# WiFi_DAC2.net
KiCad netlist of a schematic drawn in EAGLE
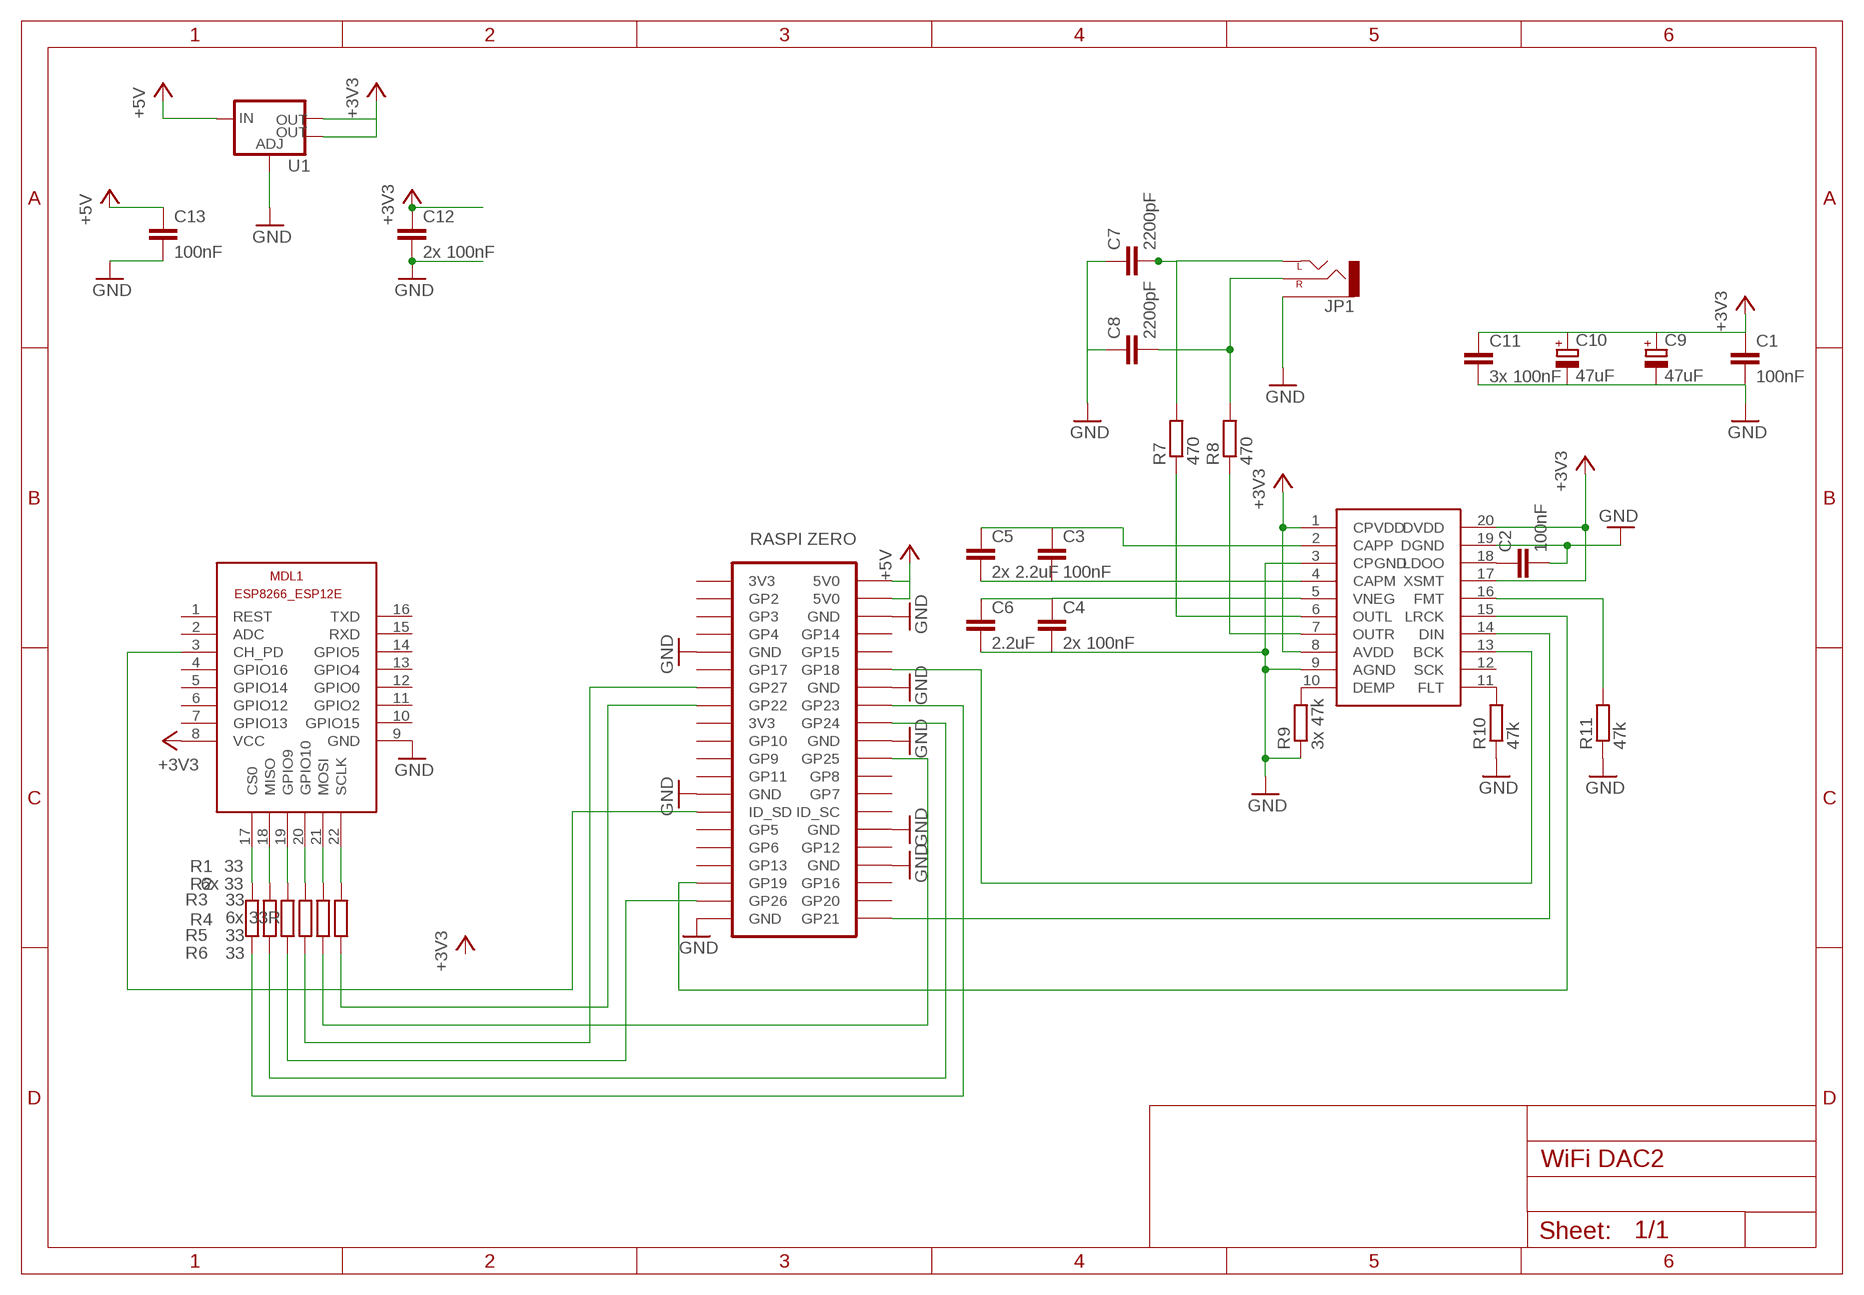
[diagram p0: schematic, sheet 1]

(export (version "E")
  (design (tool "Eeschema 10.0.6"))
  (components
    (comp (ref "C1")
      (value "100nF")
      (footprint "eagle-import:C0603")
      (libsource (lib "eagle-import") (part "C-EUC0603"))
    )
    (comp (ref "C2")
      (value "100nF")
      (footprint "eagle-import:C0603")
      (libsource (lib "eagle-import") (part "C-EUC0603"))
    )
    (comp (ref "C3")
      (value "100nF")
      (footprint "eagle-import:C0603")
      (libsource (lib "eagle-import") (part "C-EUC0603"))
    )
    (comp (ref "C4")
      (value "2x 100nF")
      (footprint "eagle-import:C0603")
      (libsource (lib "eagle-import") (part "C-EUC0603"))
    )
    (comp (ref "C5")
      (value "2x 2.2uF")
      (footprint "eagle-import:C0603")
      (libsource (lib "eagle-import") (part "C-EUC0603"))
    )
    (comp (ref "C6")
      (value "2.2uF")
      (footprint "eagle-import:C0603")
      (libsource (lib "eagle-import") (part "C-EUC0603"))
    )
    (comp (ref "C7")
      (value "2200pF")
      (footprint "eagle-import:C0603")
      (libsource (lib "eagle-import") (part "C-EUC0603"))
    )
    (comp (ref "C8")
      (value "2200pF")
      (footprint "eagle-import:C0603")
      (libsource (lib "eagle-import") (part "C-EUC0603"))
    )
    (comp (ref "C9")
      (value "47uF")
      (footprint "eagle-import:SANYO-OSCON_SMD_A5")
      (libsource (lib "eagle-import") (part "CPOL-EUSANYO_SMD_A5"))
    )
    (comp (ref "C10")
      (value "47uF")
      (footprint "eagle-import:SANYO-OSCON_SMD_A5")
      (libsource (lib "eagle-import") (part "CPOL-EUSANYO_SMD_A5"))
    )
    (comp (ref "C11")
      (value "3x 100nF")
      (footprint "eagle-import:C0603")
      (libsource (lib "eagle-import") (part "C-EUC0603"))
    )
    (comp (ref "C12")
      (value "2x 100nF")
      (footprint "eagle-import:C0603")
      (libsource (lib "eagle-import") (part "C-EUC0603"))
    )
    (comp (ref "C13")
      (value "100nF")
      (footprint "eagle-import:C0603")
      (libsource (lib "eagle-import") (part "C-EUC0603"))
    )
    (comp (ref "JP1")
      (value "AUDIO-JACKPTH")
      (footprint "eagle-import:AUDIO-JACK")
      (libsource (lib "eagle-import") (part "AUDIO-JACKPTH"))
    )
    (comp (ref "MDL1")
      (value "ESP8266-12EESP8266-ESP12E")
      (footprint "eagle-import:ESP8266-ESP12E")
      (libsource (lib "eagle-import") (part "ESP8266-12EESP8266-ESP12E"))
    )
    (comp (ref "R1")
      (value "33")
      (footprint "eagle-import:R0603")
      (libsource (lib "eagle-import") (part "R-EU_R0603"))
    )
    (comp (ref "R2")
      (value "6x 33")
      (footprint "eagle-import:R0603")
      (libsource (lib "eagle-import") (part "R-EU_R0603"))
    )
    (comp (ref "R3")
      (value "33")
      (footprint "eagle-import:R0603")
      (libsource (lib "eagle-import") (part "R-EU_R0603"))
    )
    (comp (ref "R4")
      (value "6x 33R")
      (footprint "eagle-import:R0603")
      (libsource (lib "eagle-import") (part "R-EU_R0603"))
    )
    (comp (ref "R5")
      (value "33")
      (footprint "eagle-import:R0603")
      (libsource (lib "eagle-import") (part "R-EU_R0603"))
    )
    (comp (ref "R6")
      (value "33")
      (footprint "eagle-import:R0603")
      (libsource (lib "eagle-import") (part "R-EU_R0603"))
    )
    (comp (ref "R7")
      (value "470")
      (footprint "eagle-import:R0603")
      (libsource (lib "eagle-import") (part "R-EU_R0603"))
    )
    (comp (ref "R8")
      (value "470")
      (footprint "eagle-import:R0603")
      (libsource (lib "eagle-import") (part "R-EU_R0603"))
    )
    (comp (ref "R9")
      (value "3x 47k")
      (footprint "eagle-import:R0603")
      (libsource (lib "eagle-import") (part "R-EU_R0603"))
    )
    (comp (ref "R10")
      (value "47k")
      (footprint "eagle-import:R0603")
      (libsource (lib "eagle-import") (part "R-EU_R0603"))
    )
    (comp (ref "R11")
      (value "47k")
      (footprint "eagle-import:R0603")
      (libsource (lib "eagle-import") (part "R-EU_R0603"))
    )
    (comp (ref "U$1")
      (value "ZERO")
      (footprint "eagle-import:ZERO")
      (libsource (lib "eagle-import") (part "ZERO"))
    )
    (comp (ref "U$2")
      (value "PCM5102")
      (footprint "eagle-import:TSSOP20")
      (libsource (lib "eagle-import") (part "PCM5102"))
    )
    (comp (ref "U1")
      (value "V_REG_LM1117SOT223")
      (footprint "eagle-import:SOT223")
      (libsource (lib "eagle-import") (part "V_REG_LM1117SOT223"))
    )
  )
  (nets
    (net (code "1") (name "+3V3") (class "Default")
      (node (ref "C1") (pin "1") (pinfunction "1_1") (pintype "passive"))
      (node (ref "C10") (pin "+") (pinfunction "+_+") (pintype "passive"))
      (node (ref "C11") (pin "1") (pinfunction "1_1") (pintype "passive"))
      (node (ref "C12") (pin "1") (pinfunction "1_1") (pintype "passive"))
      (node (ref "C9") (pin "+") (pinfunction "+_+") (pintype "passive"))
      (node (ref "MDL1") (pin "8") (pinfunction "VCC_8") (pintype "bidirectional"))
      (node (ref "U$2") (pin "1") (pinfunction "CPVDD_1") (pintype "bidirectional"))
      (node (ref "U$2") (pin "17") (pinfunction "XSMT_17") (pintype "bidirectional"))
      (node (ref "U$2") (pin "20") (pinfunction "DVDD_20") (pintype "bidirectional"))
      (node (ref "U$2") (pin "8") (pinfunction "AVDD_8") (pintype "bidirectional"))
      (node (ref "U1") (pin "2") (pinfunction "OUT_2") (pintype "output"))
      (node (ref "U1") (pin "4") (pinfunction "OUT_4") (pintype "output"))
    )
    (net (code "2") (name "+5V") (class "Default")
      (node (ref "C13") (pin "1") (pinfunction "1_1") (pintype "passive"))
      (node (ref "U$1") (pin "2") (pinfunction "5V0_2") (pintype "bidirectional"))
      (node (ref "U$1") (pin "4") (pinfunction "5V0_4") (pintype "bidirectional"))
      (node (ref "U1") (pin "3") (pinfunction "IN_3") (pintype "input"))
    )
    (net (code "3") (name "GND") (class "Default")
      (node (ref "C1") (pin "2") (pinfunction "2_2") (pintype "passive"))
      (node (ref "C10") (pin "-") (pinfunction "-_-") (pintype "passive"))
      (node (ref "C11") (pin "2") (pinfunction "2_2") (pintype "passive"))
      (node (ref "C12") (pin "2") (pinfunction "2_2") (pintype "passive"))
      (node (ref "C13") (pin "2") (pinfunction "2_2") (pintype "passive"))
      (node (ref "C2") (pin "2") (pinfunction "2_2") (pintype "passive"))
      (node (ref "C4") (pin "2") (pinfunction "2_2") (pintype "passive"))
      (node (ref "C6") (pin "2") (pinfunction "2_2") (pintype "passive"))
      (node (ref "C7") (pin "1") (pinfunction "1_1") (pintype "passive"))
      (node (ref "C8") (pin "1") (pinfunction "1_1") (pintype "passive"))
      (node (ref "C9") (pin "-") (pinfunction "-_-") (pintype "passive"))
      (node (ref "JP1") (pin "SLEEVE") (pinfunction "SLEEVE_SLEEVE") (pintype "bidirectional"))
      (node (ref "MDL1") (pin "9") (pinfunction "GND_9") (pintype "bidirectional"))
      (node (ref "R10") (pin "1") (pinfunction "1_1") (pintype "passive"))
      (node (ref "R11") (pin "1") (pinfunction "1_1") (pintype "passive"))
      (node (ref "R9") (pin "1") (pinfunction "1_1") (pintype "passive"))
      (node (ref "U$1") (pin "14") (pinfunction "GND_14") (pintype "bidirectional"))
      (node (ref "U$1") (pin "20") (pinfunction "GND_20") (pintype "bidirectional"))
      (node (ref "U$1") (pin "25") (pinfunction "GND_25") (pintype "bidirectional"))
      (node (ref "U$1") (pin "30") (pinfunction "GND_30") (pintype "bidirectional"))
      (node (ref "U$1") (pin "34") (pinfunction "GND_34") (pintype "bidirectional"))
      (node (ref "U$1") (pin "39") (pinfunction "GND_39") (pintype "bidirectional"))
      (node (ref "U$1") (pin "6") (pinfunction "GND_6") (pintype "bidirectional"))
      (node (ref "U$1") (pin "9") (pinfunction "GND_9") (pintype "bidirectional"))
      (node (ref "U$2") (pin "19") (pinfunction "DGND_19") (pintype "bidirectional"))
      (node (ref "U$2") (pin "3") (pinfunction "CPGND_3") (pintype "bidirectional"))
      (node (ref "U$2") (pin "9") (pinfunction "AGND_9") (pintype "bidirectional"))
      (node (ref "U1") (pin "1") (pinfunction "ADJ_1") (pintype "input"))
    )
    (net (code "4") (name "Net-(JP1-LEFT)") (class "Default")
      (node (ref "C7") (pin "2") (pinfunction "2_2") (pintype "passive"))
      (node (ref "JP1") (pin "TIP") (pinfunction "LEFT_TIP") (pintype "bidirectional"))
      (node (ref "R7") (pin "2") (pinfunction "2_2") (pintype "passive"))
    )
    (net (code "5") (name "Net-(JP1-RIGHT)") (class "Default")
      (node (ref "C8") (pin "2") (pinfunction "2_2") (pintype "passive"))
      (node (ref "JP1") (pin "RING") (pinfunction "RIGHT_RING") (pintype "bidirectional"))
      (node (ref "R8") (pin "2") (pinfunction "2_2") (pintype "passive"))
    )
    (net (code "6") (name "Net-(MDL1-CH_PD)") (class "Default")
      (node (ref "MDL1") (pin "3") (pinfunction "CH_PD_3") (pintype "bidirectional"))
      (node (ref "U$1") (pin "27") (pinfunction "ID_SD_27") (pintype "bidirectional"))
    )
    (net (code "7") (name "Net-(MDL1-CS0)") (class "Default")
      (node (ref "MDL1") (pin "17") (pinfunction "CS0_17") (pintype "bidirectional"))
      (node (ref "R1") (pin "2") (pinfunction "2_2") (pintype "passive"))
    )
    (net (code "8") (name "Net-(MDL1-GPIO9)") (class "Default")
      (node (ref "MDL1") (pin "19") (pinfunction "GPIO9_19") (pintype "bidirectional"))
      (node (ref "R3") (pin "2") (pinfunction "2_2") (pintype "passive"))
    )
    (net (code "9") (name "Net-(MDL1-GPIO10)") (class "Default")
      (node (ref "MDL1") (pin "20") (pinfunction "GPIO10_20") (pintype "bidirectional"))
      (node (ref "R4") (pin "2") (pinfunction "2_2") (pintype "passive"))
    )
    (net (code "10") (name "Net-(MDL1-MISO)") (class "Default")
      (node (ref "MDL1") (pin "18") (pinfunction "MISO_18") (pintype "bidirectional"))
      (node (ref "R2") (pin "2") (pinfunction "2_2") (pintype "passive"))
    )
    (net (code "11") (name "Net-(MDL1-MOSI)") (class "Default")
      (node (ref "MDL1") (pin "21") (pinfunction "MOSI_21") (pintype "bidirectional"))
      (node (ref "R5") (pin "2") (pinfunction "2_2") (pintype "passive"))
    )
    (net (code "12") (name "Net-(MDL1-SCLK)") (class "Default")
      (node (ref "MDL1") (pin "22") (pinfunction "SCLK_22") (pintype "bidirectional"))
      (node (ref "R6") (pin "2") (pinfunction "2_2") (pintype "passive"))
    )
    (net (code "13") (name "Net-(U$1-GP18)") (class "Default")
      (node (ref "U$1") (pin "12") (pinfunction "GP18_12") (pintype "bidirectional"))
      (node (ref "U$2") (pin "13") (pinfunction "BCK_13") (pintype "bidirectional"))
    )
    (net (code "14") (name "Net-(U$1-GP19)") (class "Default")
      (node (ref "U$1") (pin "35") (pinfunction "GP19_35") (pintype "bidirectional"))
      (node (ref "U$2") (pin "15") (pinfunction "LRCK_15") (pintype "bidirectional"))
    )
    (net (code "15") (name "Net-(U$1-GP21)") (class "Default")
      (node (ref "U$1") (pin "40") (pinfunction "GP21_40") (pintype "bidirectional"))
      (node (ref "U$2") (pin "14") (pinfunction "DIN_14") (pintype "bidirectional"))
    )
    (net (code "16") (name "Net-(U$1-GP22)") (class "Default")
      (node (ref "R6") (pin "1") (pinfunction "1_1") (pintype "passive"))
      (node (ref "U$1") (pin "15") (pinfunction "GP22_15") (pintype "bidirectional"))
    )
    (net (code "17") (name "Net-(U$1-GP23)") (class "Default")
      (node (ref "R1") (pin "1") (pinfunction "1_1") (pintype "passive"))
      (node (ref "U$1") (pin "16") (pinfunction "GP23_16") (pintype "bidirectional"))
    )
    (net (code "18") (name "Net-(U$1-GP24)") (class "Default")
      (node (ref "R2") (pin "1") (pinfunction "1_1") (pintype "passive"))
      (node (ref "U$1") (pin "18") (pinfunction "GP24_18") (pintype "bidirectional"))
    )
    (net (code "19") (name "Net-(U$1-GP25)") (class "Default")
      (node (ref "R5") (pin "1") (pinfunction "1_1") (pintype "passive"))
      (node (ref "U$1") (pin "22") (pinfunction "GP25_22") (pintype "bidirectional"))
    )
    (net (code "20") (name "Net-(U$1-GP26)") (class "Default")
      (node (ref "R3") (pin "1") (pinfunction "1_1") (pintype "passive"))
      (node (ref "U$1") (pin "37") (pinfunction "GP26_37") (pintype "bidirectional"))
    )
    (net (code "21") (name "Net-(U$1-GP27)") (class "Default")
      (node (ref "R4") (pin "1") (pinfunction "1_1") (pintype "passive"))
      (node (ref "U$1") (pin "13") (pinfunction "GP27_13") (pintype "bidirectional"))
    )
    (net (code "22") (name "Net-(U$2-CAPM)") (class "Default")
      (node (ref "C3") (pin "2") (pinfunction "2_2") (pintype "passive"))
      (node (ref "C5") (pin "2") (pinfunction "2_2") (pintype "passive"))
      (node (ref "U$2") (pin "4") (pinfunction "CAPM_4") (pintype "bidirectional"))
    )
    (net (code "23") (name "Net-(U$2-CAPP)") (class "Default")
      (node (ref "C3") (pin "1") (pinfunction "1_1") (pintype "passive"))
      (node (ref "C5") (pin "1") (pinfunction "1_1") (pintype "passive"))
      (node (ref "U$2") (pin "2") (pinfunction "CAPP_2") (pintype "bidirectional"))
    )
    (net (code "24") (name "Net-(U$2-DEMP)") (class "Default")
      (node (ref "R9") (pin "2") (pinfunction "2_2") (pintype "passive"))
      (node (ref "U$2") (pin "10") (pinfunction "DEMP_10") (pintype "bidirectional"))
    )
    (net (code "25") (name "Net-(U$2-FLT)") (class "Default")
      (node (ref "R10") (pin "2") (pinfunction "2_2") (pintype "passive"))
      (node (ref "U$2") (pin "11") (pinfunction "FLT_11") (pintype "bidirectional"))
    )
    (net (code "26") (name "Net-(U$2-FMT)") (class "Default")
      (node (ref "R11") (pin "2") (pinfunction "2_2") (pintype "passive"))
      (node (ref "U$2") (pin "16") (pinfunction "FMT_16") (pintype "bidirectional"))
    )
    (net (code "27") (name "Net-(U$2-LDOO)") (class "Default")
      (node (ref "C2") (pin "1") (pinfunction "1_1") (pintype "passive"))
      (node (ref "U$2") (pin "18") (pinfunction "LDOO_18") (pintype "bidirectional"))
    )
    (net (code "28") (name "Net-(U$2-OUTL)") (class "Default")
      (node (ref "R7") (pin "1") (pinfunction "1_1") (pintype "passive"))
      (node (ref "U$2") (pin "6") (pinfunction "OUTL_6") (pintype "bidirectional"))
    )
    (net (code "29") (name "Net-(U$2-OUTR)") (class "Default")
      (node (ref "R8") (pin "1") (pinfunction "1_1") (pintype "passive"))
      (node (ref "U$2") (pin "7") (pinfunction "OUTR_7") (pintype "bidirectional"))
    )
    (net (code "30") (name "Net-(U$2-VNEG)") (class "Default")
      (node (ref "C4") (pin "1") (pinfunction "1_1") (pintype "passive"))
      (node (ref "C6") (pin "1") (pinfunction "1_1") (pintype "passive"))
      (node (ref "U$2") (pin "5") (pinfunction "VNEG_5") (pintype "bidirectional"))
    )
    (net (code "31") (name "unconnected-(MDL1-ADC-Pad2)") (class "Default")
      (node (ref "MDL1") (pin "2") (pinfunction "ADC_2") (pintype "bidirectional"))
    )
    (net (code "32") (name "unconnected-(MDL1-GPIO0-Pad12)") (class "Default")
      (node (ref "MDL1") (pin "12") (pinfunction "GPIO0_12") (pintype "bidirectional"))
    )
    (net (code "33") (name "unconnected-(MDL1-GPIO2-Pad11)") (class "Default")
      (node (ref "MDL1") (pin "11") (pinfunction "GPIO2_11") (pintype "bidirectional"))
    )
    (net (code "34") (name "unconnected-(MDL1-GPIO4-Pad13)") (class "Default")
      (node (ref "MDL1") (pin "13") (pinfunction "GPIO4_13") (pintype "bidirectional"))
    )
    (net (code "35") (name "unconnected-(MDL1-GPIO5-Pad14)") (class "Default")
      (node (ref "MDL1") (pin "14") (pinfunction "GPIO5_14") (pintype "bidirectional"))
    )
    (net (code "36") (name "unconnected-(MDL1-GPIO12-Pad6)") (class "Default")
      (node (ref "MDL1") (pin "6") (pinfunction "GPIO12_6") (pintype "bidirectional"))
    )
    (net (code "37") (name "unconnected-(MDL1-GPIO13-Pad7)") (class "Default")
      (node (ref "MDL1") (pin "7") (pinfunction "GPIO13_7") (pintype "bidirectional"))
    )
    (net (code "38") (name "unconnected-(MDL1-GPIO14-Pad5)") (class "Default")
      (node (ref "MDL1") (pin "5") (pinfunction "GPIO14_5") (pintype "bidirectional"))
    )
    (net (code "39") (name "unconnected-(MDL1-GPIO15-Pad10)") (class "Default")
      (node (ref "MDL1") (pin "10") (pinfunction "GPIO15_10") (pintype "bidirectional"))
    )
    (net (code "40") (name "unconnected-(MDL1-GPIO16-Pad4)") (class "Default")
      (node (ref "MDL1") (pin "4") (pinfunction "GPIO16_4") (pintype "bidirectional"))
    )
    (net (code "41") (name "unconnected-(MDL1-REST-Pad1)") (class "Default")
      (node (ref "MDL1") (pin "1") (pinfunction "REST_1") (pintype "bidirectional"))
    )
    (net (code "42") (name "unconnected-(MDL1-RXD-Pad15)") (class "Default")
      (node (ref "MDL1") (pin "15") (pinfunction "RXD_15") (pintype "bidirectional"))
    )
    (net (code "43") (name "unconnected-(MDL1-TXD-Pad16)") (class "Default")
      (node (ref "MDL1") (pin "16") (pinfunction "TXD_16") (pintype "bidirectional"))
    )
    (net (code "44") (name "unconnected-(U$1-3V3-Pad1)") (class "Default")
      (node (ref "U$1") (pin "1") (pinfunction "3V3_1") (pintype "bidirectional"))
    )
    (net (code "45") (name "unconnected-(U$1-3V3-Pad17)") (class "Default")
      (node (ref "U$1") (pin "17") (pinfunction "3V3_17") (pintype "bidirectional"))
    )
    (net (code "46") (name "unconnected-(U$1-GP2-Pad3)") (class "Default")
      (node (ref "U$1") (pin "3") (pinfunction "GP2_3") (pintype "bidirectional"))
    )
    (net (code "47") (name "unconnected-(U$1-GP3-Pad5)") (class "Default")
      (node (ref "U$1") (pin "5") (pinfunction "GP3_5") (pintype "bidirectional"))
    )
    (net (code "48") (name "unconnected-(U$1-GP4-Pad7)") (class "Default")
      (node (ref "U$1") (pin "7") (pinfunction "GP4_7") (pintype "bidirectional"))
    )
    (net (code "49") (name "unconnected-(U$1-GP5-Pad29)") (class "Default")
      (node (ref "U$1") (pin "29") (pinfunction "GP5_29") (pintype "bidirectional"))
    )
    (net (code "50") (name "unconnected-(U$1-GP6-Pad31)") (class "Default")
      (node (ref "U$1") (pin "31") (pinfunction "GP6_31") (pintype "bidirectional"))
    )
    (net (code "51") (name "unconnected-(U$1-GP7-Pad26)") (class "Default")
      (node (ref "U$1") (pin "26") (pinfunction "GP7_26") (pintype "bidirectional"))
    )
    (net (code "52") (name "unconnected-(U$1-GP8-Pad24)") (class "Default")
      (node (ref "U$1") (pin "24") (pinfunction "GP8_24") (pintype "bidirectional"))
    )
    (net (code "53") (name "unconnected-(U$1-GP9-Pad21)") (class "Default")
      (node (ref "U$1") (pin "21") (pinfunction "GP9_21") (pintype "bidirectional"))
    )
    (net (code "54") (name "unconnected-(U$1-GP10-Pad19)") (class "Default")
      (node (ref "U$1") (pin "19") (pinfunction "GP10_19") (pintype "bidirectional"))
    )
    (net (code "55") (name "unconnected-(U$1-GP11-Pad23)") (class "Default")
      (node (ref "U$1") (pin "23") (pinfunction "GP11_23") (pintype "bidirectional"))
    )
    (net (code "56") (name "unconnected-(U$1-GP12-Pad32)") (class "Default")
      (node (ref "U$1") (pin "32") (pinfunction "GP12_32") (pintype "bidirectional"))
    )
    (net (code "57") (name "unconnected-(U$1-GP13-Pad33)") (class "Default")
      (node (ref "U$1") (pin "33") (pinfunction "GP13_33") (pintype "bidirectional"))
    )
    (net (code "58") (name "unconnected-(U$1-GP14-Pad8)") (class "Default")
      (node (ref "U$1") (pin "8") (pinfunction "GP14_8") (pintype "bidirectional"))
    )
    (net (code "59") (name "unconnected-(U$1-GP15-Pad10)") (class "Default")
      (node (ref "U$1") (pin "10") (pinfunction "GP15_10") (pintype "bidirectional"))
    )
    (net (code "60") (name "unconnected-(U$1-GP16-Pad36)") (class "Default")
      (node (ref "U$1") (pin "36") (pinfunction "GP16_36") (pintype "bidirectional"))
    )
    (net (code "61") (name "unconnected-(U$1-GP17-Pad11)") (class "Default")
      (node (ref "U$1") (pin "11") (pinfunction "GP17_11") (pintype "bidirectional"))
    )
    (net (code "62") (name "unconnected-(U$1-GP20-Pad38)") (class "Default")
      (node (ref "U$1") (pin "38") (pinfunction "GP20_38") (pintype "bidirectional"))
    )
    (net (code "63") (name "unconnected-(U$1-ID_SC-Pad28)") (class "Default")
      (node (ref "U$1") (pin "28") (pinfunction "ID_SC_28") (pintype "bidirectional"))
    )
    (net (code "64") (name "unconnected-(U$2-SCK-Pad12)") (class "Default")
      (node (ref "U$2") (pin "12") (pinfunction "SCK_12") (pintype "bidirectional"))
    )
  )
)
